# OLM-1_0.net
KiCad netlist of a schematic drawn in EAGLE
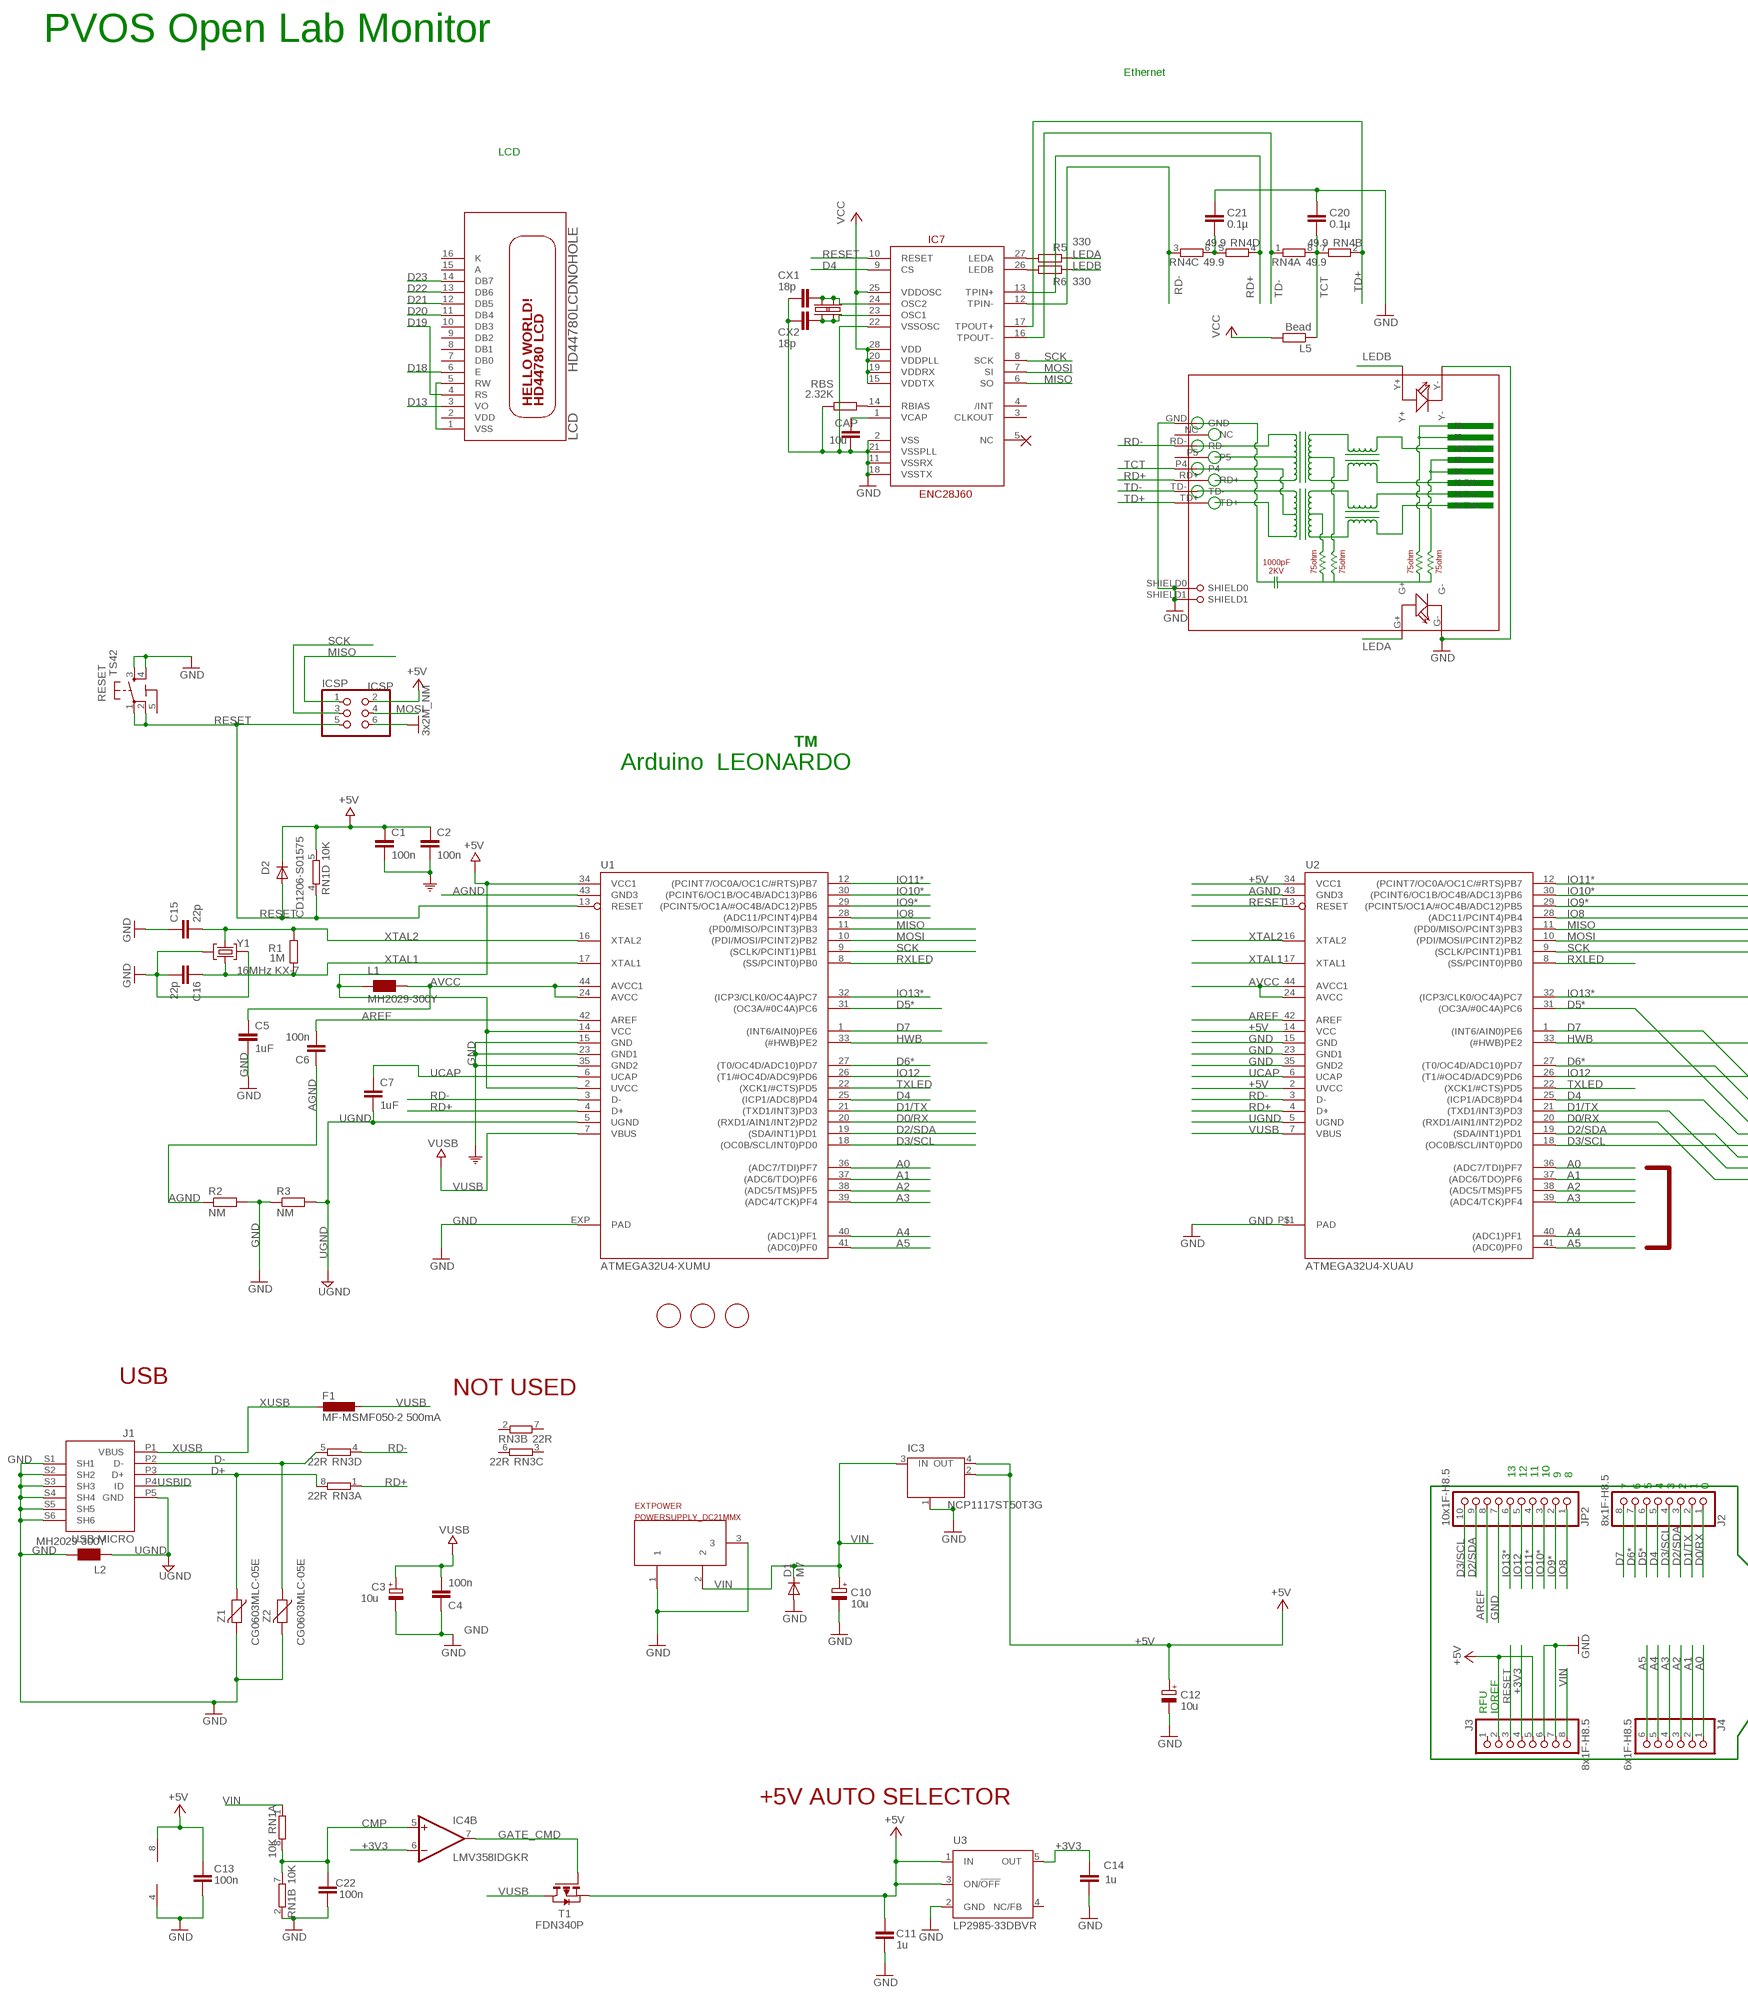
[diagram p0: schematic, sheet 1, part 1 of 2]
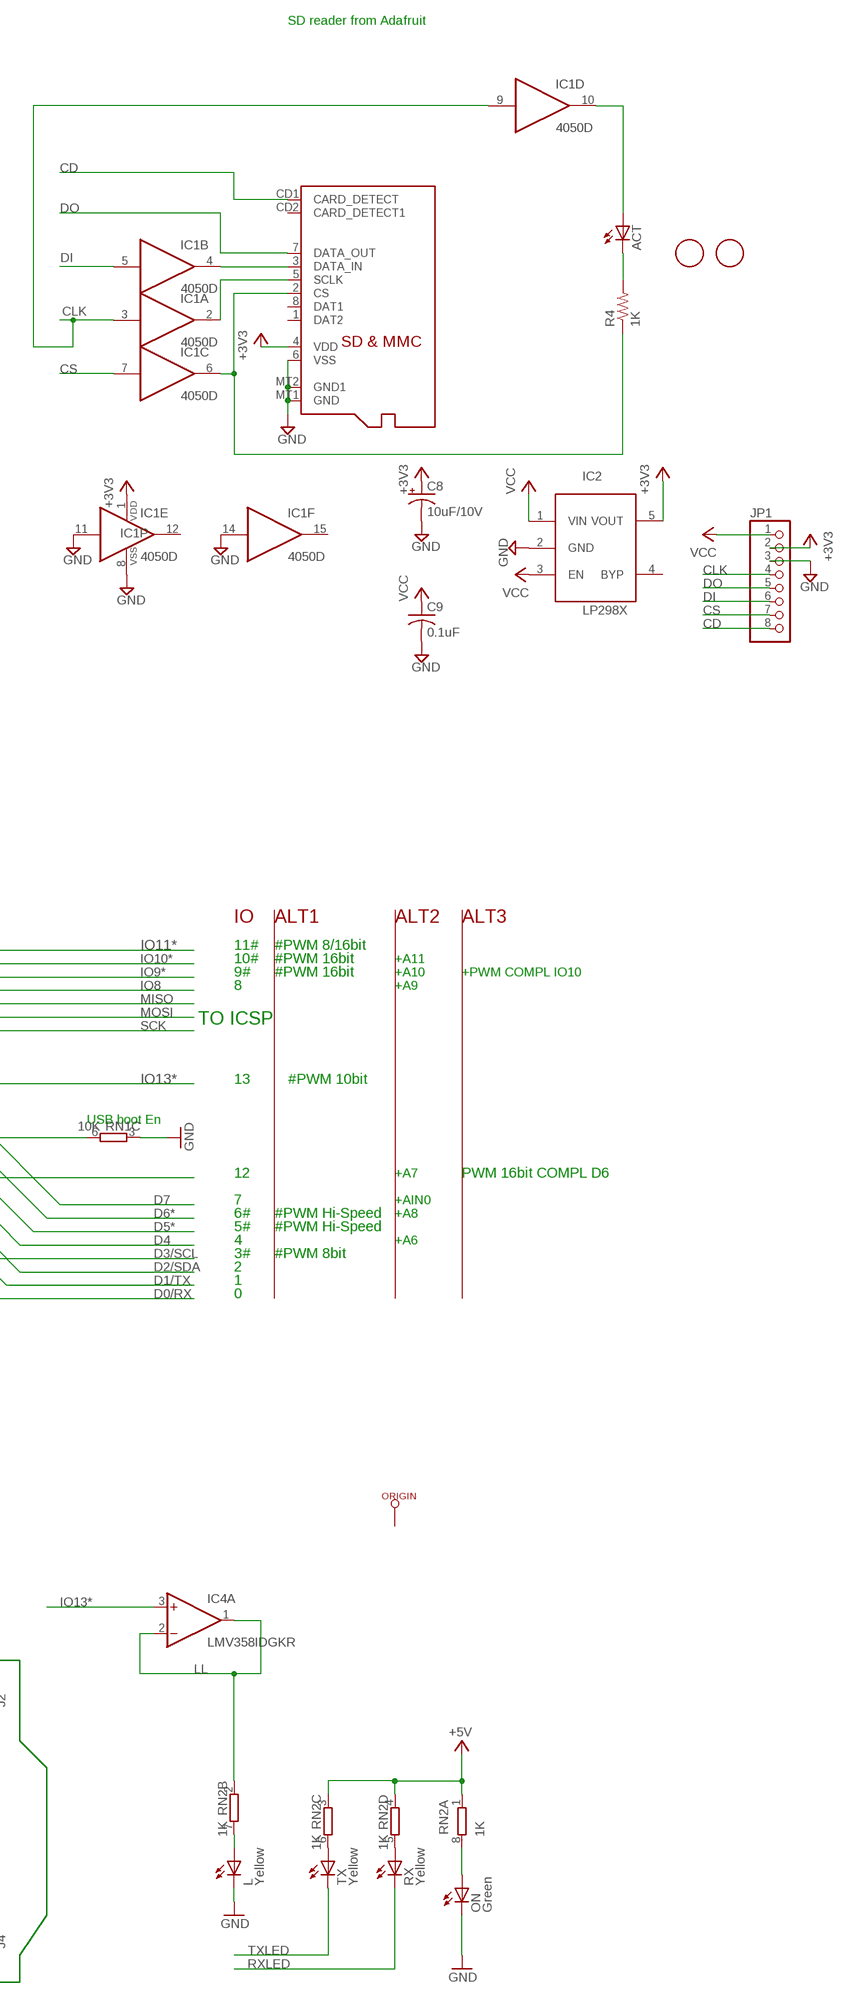
[diagram p1: schematic, sheet 1, part 2 of 2]

(export (version "E")
  (design (tool "Eeschema 10.0.6"))
  (components
    (comp (ref "ACT")
      (value "LEDCHIP-LED0805")
      (footprint "eagle-import:CHIP-LED0805")
      (libsource (lib "eagle-import") (part "LEDCHIP-LED0805"))
    )
    (comp (ref "C1")
      (value "100n")
      (footprint "eagle-import:C0603-ROUND")
      (libsource (lib "eagle-import") (part "C-EUC0603"))
    )
    (comp (ref "C2")
      (value "100n")
      (footprint "eagle-import:C0603-ROUND")
      (libsource (lib "eagle-import") (part "C-EUC0603"))
    )
    (comp (ref "C3")
      (value "10u")
      (footprint "eagle-import:SMC_B")
      (libsource (lib "eagle-import") (part "CPOL-EUSMCB"))
    )
    (comp (ref "C4")
      (value "100n")
      (footprint "eagle-import:C0603-ROUND")
      (libsource (lib "eagle-import") (part "C-EUC0603"))
    )
    (comp (ref "C5")
      (value "1uF")
      (footprint "eagle-import:C0603-ROUND")
      (libsource (lib "eagle-import") (part "C-EUC0603"))
    )
    (comp (ref "C6")
      (value "100n")
      (footprint "eagle-import:C0603-ROUND")
      (libsource (lib "eagle-import") (part "C-EUC0603"))
    )
    (comp (ref "C7")
      (value "1uF")
      (footprint "eagle-import:C0603-ROUND")
      (libsource (lib "eagle-import") (part "C-EUC0603"))
    )
    (comp (ref "C8")
      (value "10uF/10V")
      (footprint "eagle-import:A_3216-18R")
      (libsource (lib "eagle-import") (part "CPOL-USA/3216-18R"))
    )
    (comp (ref "C9")
      (value "0.1uF")
      (footprint "eagle-import:C0805K")
      (libsource (lib "eagle-import") (part "C-USC0805K"))
    )
    (comp (ref "C10")
      (value "10u")
      (footprint "eagle-import:SMC_B")
      (libsource (lib "eagle-import") (part "CPOL-EUSMCB"))
    )
    (comp (ref "C11")
      (value "1u")
      (footprint "eagle-import:C0603-ROUND")
      (libsource (lib "eagle-import") (part "C-EUC0603"))
    )
    (comp (ref "C12")
      (value "10u")
      (footprint "eagle-import:SMC_B")
      (libsource (lib "eagle-import") (part "CPOL-EUSMCB"))
    )
    (comp (ref "C13")
      (value "100n")
      (footprint "eagle-import:C0603-ROUND")
      (libsource (lib "eagle-import") (part "C-EUC0603"))
    )
    (comp (ref "C14")
      (value "1u")
      (footprint "eagle-import:C0603-ROUND")
      (libsource (lib "eagle-import") (part "C-EUC0603"))
    )
    (comp (ref "C15")
      (value "22p")
      (footprint "eagle-import:C0603-ROUND")
      (libsource (lib "eagle-import") (part "C-EUC0603"))
    )
    (comp (ref "C16")
      (value "22p")
      (footprint "eagle-import:C0603-ROUND")
      (libsource (lib "eagle-import") (part "C-EUC0603"))
    )
    (comp (ref "C20")
      (value "0.1µ")
      (footprint "eagle-import:C0805")
      (libsource (lib "eagle-import") (part "resistor_C-EUC0805"))
    )
    (comp (ref "C21")
      (value "0.1µ")
      (footprint "eagle-import:C0805")
      (libsource (lib "eagle-import") (part "resistor_C-EUC0805"))
    )
    (comp (ref "C22")
      (value "100n")
      (footprint "eagle-import:C0603-ROUND")
      (libsource (lib "eagle-import") (part "C-EUC0603"))
    )
    (comp (ref "CAP")
      (value "10u")
      (footprint "eagle-import:C0805")
      (libsource (lib "eagle-import") (part "resistor_C-EUC0805"))
    )
    (comp (ref "CX1")
      (value "18p")
      (footprint "eagle-import:C0805")
      (libsource (lib "eagle-import") (part "resistor_C-EUC0805"))
    )
    (comp (ref "CX2")
      (value "18p")
      (footprint "eagle-import:C0805")
      (libsource (lib "eagle-import") (part "resistor_C-EUC0805"))
    )
    (comp (ref "D1")
      (value "M7")
      (footprint "eagle-import:SMB")
      (libsource (lib "eagle-import") (part "DIODE-SMB"))
    )
    (comp (ref "D2")
      (value "CD1206-S01575")
      (footprint "eagle-import:MINIMELF")
      (libsource (lib "eagle-import") (part "DIODE-MINIMELF"))
    )
    (comp (ref "EXTPOWER")
      (value "POWERSUPPLY_DC21MMX")
      (footprint "eagle-import:POWERSUPPLY_DC-21MM")
      (libsource (lib "eagle-import") (part "POWERSUPPLY_DC21MMX"))
    )
    (comp (ref "F1")
      (value "MF-MSMF050-2 500mA")
      (footprint "eagle-import:L1812")
      (libsource (lib "eagle-import") (part "L-EUL1812"))
    )
    (comp (ref "FID1")
      (value "FIDUCIALMOUNT")
      (footprint "eagle-import:FIDUCIA-MOUNT")
      (libsource (lib "eagle-import") (part "FIDUCIALMOUNT"))
    )
    (comp (ref "FID2")
      (value "FIDUCIALMOUNT")
      (footprint "eagle-import:FIDUCIA-MOUNT")
      (libsource (lib "eagle-import") (part "FIDUCIALMOUNT"))
    )
    (comp (ref "FID3")
      (value "FIDUCIALMOUNT")
      (footprint "eagle-import:FIDUCIA-MOUNT")
      (libsource (lib "eagle-import") (part "FIDUCIALMOUNT"))
    )
    (comp (ref "IC1")
      (value "4050D")
      (footprint "eagle-import:SO16")
      (libsource (lib "eagle-import") (part "4050D"))
    )
    (comp (ref "IC2")
      (value "LP298XS")
      (footprint "eagle-import:SOT23-5L")
      (libsource (lib "eagle-import") (part "LP298XS"))
    )
    (comp (ref "IC3")
      (value "NCP1117ST50T3G")
      (footprint "eagle-import:SOT223")
      (libsource (lib "eagle-import") (part "MC33269ST-3.3T3"))
    )
    (comp (ref "IC4")
      (value "LMV358IDGKR")
      (footprint "eagle-import:MSOP08")
      (libsource (lib "eagle-import") (part "LMV358?MMX"))
    )
    (comp (ref "IC7")
      (value "ENC28J60")
      (footprint "eagle-import:SOIC28WLONG")
      (libsource (lib "eagle-import") (part "ENC28J60SO28LONG"))
    )
    (comp (ref "ICSP")
      (value "ICSP")
      (footprint "eagle-import:2X03")
      (libsource (lib "eagle-import") (part "PINHD-2X3"))
    )
    (comp (ref "J1")
      (value "USB MICRO")
      (footprint "eagle-import:CON2_USB_MICRO_B_AT")
      (libsource (lib "eagle-import") (part "MYCON2_USB-MINI-B"))
    )
    (comp (ref "J2")
      (value "8x1F-H8.5")
      (footprint "eagle-import:1X08")
      (libsource (lib "eagle-import") (part "PINHD-1X8"))
    )
    (comp (ref "J3")
      (value "8x1F-H8.5")
      (footprint "eagle-import:1X08")
      (libsource (lib "eagle-import") (part "PINHD-1X8"))
    )
    (comp (ref "J4")
      (value "6x1F-H8.5")
      (footprint "eagle-import:1X06")
      (libsource (lib "eagle-import") (part "PINHD-1X6"))
    )
    (comp (ref "JP1")
      (value "PINHD-1X8BIG")
      (footprint "eagle-import:1X08-BIG")
      (libsource (lib "eagle-import") (part "PINHD-1X8BIG"))
    )
    (comp (ref "JP2")
      (value "10x1F-H8.5")
      (footprint "eagle-import:1X10")
      (libsource (lib "eagle-import") (part "PINHD-1X10"))
    )
    (comp (ref "L")
      (value "Yellow")
      (footprint "eagle-import:CHIPLED_0805")
      (libsource (lib "eagle-import") (part "led_LEDCHIPLED_0805"))
    )
    (comp (ref "L1")
      (value "MH2029-300Y")
      (footprint "eagle-import:0805")
      (libsource (lib "eagle-import") (part "WE-CBF_0805"))
    )
    (comp (ref "L2")
      (value "MH2029-300Y")
      (footprint "eagle-import:0805")
      (libsource (lib "eagle-import") (part "WE-CBF_0805"))
    )
    (comp (ref "L5")
      (value "Bead")
      (footprint "eagle-import:R0805")
      (libsource (lib "eagle-import") (part "rcl_R-EU_R0805"))
    )
    (comp (ref "LCD")
      (value "HD44780LCDNOHOLE")
      (footprint "eagle-import:LCD1602A")
      (libsource (lib "eagle-import") (part "HD44780LCDNOHOLE"))
    )
    (comp (ref "ON")
      (value "Green")
      (footprint "eagle-import:CHIPLED_0805")
      (libsource (lib "eagle-import") (part "led_LEDCHIPLED_0805"))
    )
    (comp (ref "ORIGIN")
      (value "TP_SP")
      (footprint "eagle-import:TP-SP")
      (libsource (lib "eagle-import") (part "TP_SP"))
    )
    (comp (ref "R1")
      (value "1M")
      (footprint "eagle-import:R0603-ROUND")
      (libsource (lib "eagle-import") (part "R-EU_R0603"))
    )
    (comp (ref "R2")
      (value "NM")
      (footprint "eagle-import:R0402")
      (libsource (lib "eagle-import") (part "R-EU_R0402"))
    )
    (comp (ref "R3")
      (value "NM")
      (footprint "eagle-import:R0402")
      (libsource (lib "eagle-import") (part "R-EU_R0402"))
    )
    (comp (ref "R4")
      (value "1K")
      (footprint "eagle-import:R0805")
      (libsource (lib "eagle-import") (part "R-US_R0805"))
    )
    (comp (ref "R5")
      (value "330")
      (footprint "eagle-import:R0805")
      (libsource (lib "eagle-import") (part "rcl_R-EU_R0805"))
    )
    (comp (ref "R6")
      (value "330")
      (footprint "eagle-import:R0805")
      (libsource (lib "eagle-import") (part "rcl_R-EU_R0805"))
    )
    (comp (ref "RBS")
      (value "2.32K")
      (footprint "eagle-import:R0805")
      (libsource (lib "eagle-import") (part "rcl_R-EU_R0805"))
    )
    (comp (ref "RESET")
      (value "TS42")
      (footprint "eagle-import:TS42")
      (libsource (lib "eagle-import") (part "TS42"))
    )
    (comp (ref "RJ1")
      (value "HR911105A")
      (footprint "eagle-import:HR911105A")
      (libsource (lib "eagle-import") (part "HR911105A"))
    )
    (comp (ref "RN1")
      (value "10K")
      (footprint "eagle-import:CAY16")
      (libsource (lib "eagle-import") (part "4R-NCAY16"))
    )
    (comp (ref "RN2")
      (value "1K")
      (footprint "eagle-import:CAY16")
      (libsource (lib "eagle-import") (part "4R-NCAY16"))
    )
    (comp (ref "RN3")
      (value "22R")
      (footprint "eagle-import:CAY16")
      (libsource (lib "eagle-import") (part "4R-NCAY16"))
    )
    (comp (ref "RN4")
      (value "49.9")
      (footprint "eagle-import:EXB38V")
      (libsource (lib "eagle-import") (part "4R-NEXB38V"))
    )
    (comp (ref "RX")
      (value "Yellow")
      (footprint "eagle-import:CHIPLED_0805")
      (libsource (lib "eagle-import") (part "led_LEDCHIPLED_0805"))
    )
    (comp (ref "T1")
      (value "FDN340P")
      (footprint "eagle-import:SOT-23")
      (libsource (lib "eagle-import") (part "PMOSSOT23"))
    )
    (comp (ref "TX")
      (value "Yellow")
      (footprint "eagle-import:CHIPLED_0805")
      (libsource (lib "eagle-import") (part "led_LEDCHIPLED_0805"))
    )
    (comp (ref "U$1")
      (value "FIDUCIAL")
      (footprint "eagle-import:FIDUCIAL_1MM")
      (libsource (lib "eagle-import") (part "FIDUCIAL"))
    )
    (comp (ref "U$2")
      (value "FIDUCIAL")
      (footprint "eagle-import:FIDUCIAL_1MM")
      (libsource (lib "eagle-import") (part "FIDUCIAL"))
    )
    (comp (ref "U1")
      (value "ATMEGA32U4-XUMU")
      (footprint "eagle-import:QFN44ML7X7")
      (libsource (lib "eagle-import") (part "ATMEGA32U4-XUMU"))
    )
    (comp (ref "U2")
      (value "ATMEGA32U4-XUAU")
      (footprint "eagle-import:TQFP44-PAD")
      (libsource (lib "eagle-import") (part "ATMEGA32U4-XUAU"))
    )
    (comp (ref "U3")
      (value "LP2985-33DBVR")
      (footprint "eagle-import:SOT23-DBV")
      (libsource (lib "eagle-import") (part "LP2985-XXDBVR33"))
    )
    (comp (ref "X1")
      (value "MICROSD")
      (footprint "eagle-import:MICROSD")
      (libsource (lib "eagle-import") (part "MICROSD"))
    )
    (comp (ref "X2A")
      (value "25MHz")
      (footprint "eagle-import:CRYSTAL-SMD-10.5X4.8-2PIN")
      (libsource (lib "eagle-import") (part "CRYSTAL10.5X4.8"))
    )
    (comp (ref "X2A1")
      (value "25MHz")
      (footprint "eagle-import:HC49US")
      (libsource (lib "eagle-import") (part "CRYSTALHC49US"))
    )
    (comp (ref "Y1")
      (value "16MHz KX-7")
      (footprint "eagle-import:CRYSTAL-3.2-2.5")
      (libsource (lib "eagle-import") (part "CRYSTAL-3.2-2.5"))
    )
    (comp (ref "Z1")
      (value "CG0603MLC-05E")
      (footprint "eagle-import:CT_CN0603")
      (libsource (lib "eagle-import") (part "VARISTORCN0603"))
    )
    (comp (ref "Z2")
      (value "CG0603MLC-05E")
      (footprint "eagle-import:CT_CN0603")
      (libsource (lib "eagle-import") (part "VARISTORCN0603"))
    )
  )
  (nets
    (net (code "1") (name "+3V3") (class "Default")
      (node (ref "C14") (pin "2") (pinfunction "2_2") (pintype "passive"))
      (node (ref "C8") (pin "+") (pinfunction "+_+") (pintype "passive"))
      (node (ref "IC1") (pin "1") (pinfunction "VDD_1") (pintype "power_in"))
      (node (ref "IC2") (pin "5") (pinfunction "VOUT_5") (pintype "bidirectional"))
      (node (ref "IC4") (pin "6") (pinfunction "-IN_6") (pintype "input"))
      (node (ref "J3") (pin "4") (pinfunction "4_4") (pintype "passive"))
      (node (ref "JP1") (pin "2") (pinfunction "2_2") (pintype "passive"))
      (node (ref "U3") (pin "5") (pinfunction "OUT_5") (pintype "passive"))
      (node (ref "X1") (pin "4") (pinfunction "VDD_4") (pintype "power_in"))
    )
    (net (code "2") (name "+5V") (class "Default")
      (node (ref "C1") (pin "1") (pinfunction "1_1") (pintype "passive"))
      (node (ref "C11") (pin "2") (pinfunction "2_2") (pintype "passive"))
      (node (ref "C12") (pin "+") (pinfunction "+_+") (pintype "passive"))
      (node (ref "C13") (pin "1") (pinfunction "1_1") (pintype "passive"))
      (node (ref "C2") (pin "1") (pinfunction "1_1") (pintype "passive"))
      (node (ref "D2") (pin "C") (pinfunction "C_C") (pintype "passive"))
      (node (ref "IC3") (pin "2") (pinfunction "OUT_2") (pintype "passive"))
      (node (ref "IC3") (pin "4") (pinfunction "OUT_4") (pintype "passive"))
      (node (ref "IC4") (pin "8") (pinfunction "V+_8") (pintype "power_in"))
      (node (ref "ICSP") (pin "2") (pinfunction "2_2") (pintype "passive"))
      (node (ref "J3") (pin "2") (pinfunction "2_2") (pintype "passive"))
      (node (ref "J3") (pin "5") (pinfunction "5_5") (pintype "passive"))
      (node (ref "L1") (pin "1") (pinfunction "1_1") (pintype "passive"))
      (node (ref "RN1") (pin "5") (pinfunction "2_5") (pintype "passive"))
      (node (ref "RN2") (pin "1") (pinfunction "1_1") (pintype "passive"))
      (node (ref "RN2") (pin "3") (pinfunction "1_3") (pintype "passive"))
      (node (ref "RN2") (pin "4") (pinfunction "1_4") (pintype "passive"))
      (node (ref "T1") (pin "2") (pinfunction "S_2") (pintype "passive"))
      (node (ref "U1") (pin "14") (pinfunction "VCC_14") (pintype "power_in"))
      (node (ref "U1") (pin "2") (pinfunction "UVCC_2") (pintype "power_in"))
      (node (ref "U1") (pin "34") (pinfunction "VCC1_34") (pintype "power_in"))
      (node (ref "U2") (pin "14") (pinfunction "VCC_14") (pintype "power_in"))
      (node (ref "U2") (pin "2") (pinfunction "UVCC_2") (pintype "power_in"))
      (node (ref "U2") (pin "34") (pinfunction "VCC1_34") (pintype "power_in"))
      (node (ref "U3") (pin "1") (pinfunction "IN_1") (pintype "input"))
      (node (ref "U3") (pin "3") (pinfunction "ON/~{OFF}_3") (pintype "input"))
    )
    (net (code "3") (name "/5-GND") (class "Default")
      (node (ref "RESET") (pin "5") (pinfunction "5-GND_5") (pintype "power_in"))
    )
    (net (code "4") (name "/A0") (class "Default")
      (node (ref "J4") (pin "1") (pinfunction "1_1") (pintype "passive"))
      (node (ref "U1") (pin "36") (pinfunction "(ADC7/TDI)PF7_36") (pintype "bidirectional"))
      (node (ref "U2") (pin "36") (pinfunction "(ADC7/TDI)PF7_36") (pintype "bidirectional"))
    )
    (net (code "5") (name "/A1") (class "Default")
      (node (ref "J4") (pin "2") (pinfunction "2_2") (pintype "passive"))
      (node (ref "U1") (pin "37") (pinfunction "(ADC6/TDO)PF6_37") (pintype "bidirectional"))
      (node (ref "U2") (pin "37") (pinfunction "(ADC6/TDO)PF6_37") (pintype "bidirectional"))
    )
    (net (code "6") (name "/A2") (class "Default")
      (node (ref "J4") (pin "3") (pinfunction "3_3") (pintype "passive"))
      (node (ref "U1") (pin "38") (pinfunction "(ADC5/TMS)PF5_38") (pintype "bidirectional"))
      (node (ref "U2") (pin "38") (pinfunction "(ADC5/TMS)PF5_38") (pintype "bidirectional"))
    )
    (net (code "7") (name "/A3") (class "Default")
      (node (ref "J4") (pin "4") (pinfunction "4_4") (pintype "passive"))
      (node (ref "U1") (pin "39") (pinfunction "(ADC4/TCK)PF4_39") (pintype "bidirectional"))
      (node (ref "U2") (pin "39") (pinfunction "(ADC4/TCK)PF4_39") (pintype "bidirectional"))
    )
    (net (code "8") (name "/A4") (class "Default")
      (node (ref "J4") (pin "5") (pinfunction "5_5") (pintype "passive"))
      (node (ref "U1") (pin "40") (pinfunction "(ADC1)PF1_40") (pintype "bidirectional"))
      (node (ref "U2") (pin "40") (pinfunction "(ADC1)PF1_40") (pintype "bidirectional"))
    )
    (net (code "9") (name "/A5") (class "Default")
      (node (ref "J4") (pin "6") (pinfunction "6_6") (pintype "passive"))
      (node (ref "U1") (pin "41") (pinfunction "(ADC0)PF0_41") (pintype "bidirectional"))
      (node (ref "U2") (pin "41") (pinfunction "(ADC0)PF0_41") (pintype "bidirectional"))
    )
    (net (code "10") (name "/AGND") (class "Default")
      (node (ref "C6") (pin "1") (pinfunction "1_1") (pintype "passive"))
      (node (ref "R2") (pin "1") (pinfunction "1_1") (pintype "passive"))
      (node (ref "U1") (pin "43") (pinfunction "GND3_43") (pintype "power_in"))
      (node (ref "U2") (pin "43") (pinfunction "GND3_43") (pintype "power_in"))
    )
    (net (code "11") (name "/AREF") (class "Default")
      (node (ref "C6") (pin "2") (pinfunction "2_2") (pintype "passive"))
      (node (ref "JP2") (pin "8") (pinfunction "8_8") (pintype "passive"))
      (node (ref "U1") (pin "42") (pinfunction "AREF_42") (pintype "power_in"))
      (node (ref "U2") (pin "42") (pinfunction "AREF_42") (pintype "power_in"))
    )
    (net (code "12") (name "/AVCC") (class "Default")
      (node (ref "C5") (pin "1") (pinfunction "1_1") (pintype "passive"))
      (node (ref "L1") (pin "2") (pinfunction "2_2") (pintype "passive"))
      (node (ref "U1") (pin "24") (pinfunction "AVCC_24") (pintype "power_in"))
      (node (ref "U1") (pin "44") (pinfunction "AVCC1_44") (pintype "power_in"))
      (node (ref "U2") (pin "24") (pinfunction "AVCC_24") (pintype "power_in"))
      (node (ref "U2") (pin "44") (pinfunction "AVCC1_44") (pintype "power_in"))
    )
    (net (code "13") (name "/CD") (class "Default")
      (node (ref "JP1") (pin "8") (pinfunction "8_8") (pintype "passive"))
      (node (ref "X1") (pin "CD1") (pinfunction "CARD_DETECT_CD1") (pintype "passive"))
    )
    (net (code "14") (name "/CLK") (class "Default")
      (node (ref "IC1") (pin "3") (pinfunction "I_3") (pintype "input"))
      (node (ref "IC1") (pin "9") (pinfunction "I_9") (pintype "input"))
      (node (ref "JP1") (pin "4") (pinfunction "4_4") (pintype "passive"))
    )
    (net (code "15") (name "/CMP") (class "Default")
      (node (ref "C22") (pin "2") (pinfunction "2_2") (pintype "passive"))
      (node (ref "IC4") (pin "5") (pinfunction "+IN_5") (pintype "input"))
      (node (ref "RN1") (pin "7") (pinfunction "2_7") (pintype "passive"))
      (node (ref "RN1") (pin "8") (pinfunction "2_8") (pintype "passive"))
    )
    (net (code "16") (name "/CS") (class "Default")
      (node (ref "IC1") (pin "7") (pinfunction "I_7") (pintype "input"))
      (node (ref "JP1") (pin "7") (pinfunction "7_7") (pintype "passive"))
    )
    (net (code "17") (name "/D+") (class "Default")
      (node (ref "J1") (pin "P3") (pinfunction "D+_P3") (pintype "bidirectional"))
      (node (ref "RN3") (pin "8") (pinfunction "2_8") (pintype "passive"))
      (node (ref "Z1") (pin "1") (pinfunction "1_1") (pintype "passive"))
    )
    (net (code "18") (name "/D-") (class "Default")
      (node (ref "J1") (pin "P2") (pinfunction "D-_P2") (pintype "bidirectional"))
      (node (ref "RN3") (pin "5") (pinfunction "2_5") (pintype "passive"))
      (node (ref "Z2") (pin "1") (pinfunction "1_1") (pintype "passive"))
    )
    (net (code "19") (name "/D0{slash}RX") (class "Default")
      (node (ref "J2") (pin "1") (pinfunction "1_1") (pintype "passive"))
      (node (ref "U1") (pin "20") (pinfunction "(RXD1/AIN1/INT2)PD2_20") (pintype "bidirectional"))
      (node (ref "U2") (pin "20") (pinfunction "(RXD1/AIN1/INT2)PD2_20") (pintype "bidirectional"))
    )
    (net (code "20") (name "/D1{slash}TX") (class "Default")
      (node (ref "J2") (pin "2") (pinfunction "2_2") (pintype "passive"))
      (node (ref "U1") (pin "21") (pinfunction "(TXD1/INT3)PD3_21") (pintype "bidirectional"))
      (node (ref "U2") (pin "21") (pinfunction "(TXD1/INT3)PD3_21") (pintype "bidirectional"))
    )
    (net (code "21") (name "/D2{slash}SDA") (class "Default")
      (node (ref "J2") (pin "3") (pinfunction "3_3") (pintype "passive"))
      (node (ref "JP2") (pin "9") (pinfunction "9_9") (pintype "passive"))
      (node (ref "U1") (pin "19") (pinfunction "(SDA/INT1)PD1_19") (pintype "bidirectional"))
      (node (ref "U2") (pin "19") (pinfunction "(SDA/INT1)PD1_19") (pintype "bidirectional"))
    )
    (net (code "22") (name "/D3{slash}SCL") (class "Default")
      (node (ref "J2") (pin "4") (pinfunction "4_4") (pintype "passive"))
      (node (ref "JP2") (pin "10") (pinfunction "10_10") (pintype "passive"))
      (node (ref "U1") (pin "18") (pinfunction "(OC0B/SCL/INT0)PD0_18") (pintype "bidirectional"))
      (node (ref "U2") (pin "18") (pinfunction "(OC0B/SCL/INT0)PD0_18") (pintype "bidirectional"))
    )
    (net (code "23") (name "/D4") (class "Default")
      (node (ref "IC7") (pin "9") (pinfunction "CS_9") (pintype "bidirectional"))
      (node (ref "J2") (pin "5") (pinfunction "5_5") (pintype "passive"))
      (node (ref "U1") (pin "25") (pinfunction "(ICP1/ADC8)PD4_25") (pintype "bidirectional"))
      (node (ref "U2") (pin "25") (pinfunction "(ICP1/ADC8)PD4_25") (pintype "bidirectional"))
    )
    (net (code "24") (name "/D5*") (class "Default")
      (node (ref "J2") (pin "6") (pinfunction "6_6") (pintype "passive"))
      (node (ref "U1") (pin "31") (pinfunction "(OC3A/#0C4A)PC6_31") (pintype "bidirectional"))
      (node (ref "U2") (pin "31") (pinfunction "(OC3A/#0C4A)PC6_31") (pintype "bidirectional"))
    )
    (net (code "25") (name "/D6*") (class "Default")
      (node (ref "J2") (pin "7") (pinfunction "7_7") (pintype "passive"))
      (node (ref "U1") (pin "27") (pinfunction "(T0/OC4D/ADC10)PD7_27") (pintype "bidirectional"))
      (node (ref "U2") (pin "27") (pinfunction "(T0/OC4D/ADC10)PD7_27") (pintype "bidirectional"))
    )
    (net (code "26") (name "/D7") (class "Default")
      (node (ref "J2") (pin "8") (pinfunction "8_8") (pintype "passive"))
      (node (ref "U1") (pin "1") (pinfunction "(INT6/AIN0)PE6_1") (pintype "bidirectional"))
      (node (ref "U2") (pin "1") (pinfunction "(INT6/AIN0)PE6_1") (pintype "bidirectional"))
    )
    (net (code "27") (name "/D13") (class "Default")
      (node (ref "LCD") (pin "3") (pinfunction "VO_3") (pintype "input"))
    )
    (net (code "28") (name "/D18") (class "Default")
      (node (ref "LCD") (pin "6") (pinfunction "E_6") (pintype "input"))
    )
    (net (code "29") (name "/D19") (class "Default")
      (node (ref "LCD") (pin "4") (pinfunction "RS_4") (pintype "input"))
    )
    (net (code "30") (name "/D20") (class "Default")
      (node (ref "LCD") (pin "11") (pinfunction "DB4_11") (pintype "bidirectional"))
    )
    (net (code "31") (name "/D21") (class "Default")
      (node (ref "LCD") (pin "12") (pinfunction "DB5_12") (pintype "bidirectional"))
    )
    (net (code "32") (name "/D22") (class "Default")
      (node (ref "LCD") (pin "13") (pinfunction "DB6_13") (pintype "bidirectional"))
    )
    (net (code "33") (name "/D23") (class "Default")
      (node (ref "LCD") (pin "14") (pinfunction "DB7_14") (pintype "bidirectional"))
    )
    (net (code "34") (name "/DI") (class "Default")
      (node (ref "IC1") (pin "5") (pinfunction "I_5") (pintype "input"))
      (node (ref "JP1") (pin "6") (pinfunction "6_6") (pintype "passive"))
    )
    (net (code "35") (name "/DO") (class "Default")
      (node (ref "JP1") (pin "5") (pinfunction "5_5") (pintype "passive"))
      (node (ref "X1") (pin "7") (pinfunction "DATA_OUT_7") (pintype "output"))
    )
    (net (code "36") (name "/GATE_CMD") (class "Default")
      (node (ref "IC4") (pin "7") (pinfunction "OUT_7") (pintype "output"))
      (node (ref "T1") (pin "3") (pinfunction "G_3") (pintype "passive"))
    )
    (net (code "37") (name "/HWB") (class "Default")
      (node (ref "RN1") (pin "6") (pinfunction "2_6") (pintype "passive"))
      (node (ref "U1") (pin "33") (pinfunction "(#HWB)PE2_33") (pintype "bidirectional"))
      (node (ref "U2") (pin "33") (pinfunction "(#HWB)PE2_33") (pintype "bidirectional"))
    )
    (net (code "38") (name "/IO8") (class "Default")
      (node (ref "JP2") (pin "1") (pinfunction "1_1") (pintype "passive"))
      (node (ref "U1") (pin "28") (pinfunction "(ADC11/PCINT4)PB4_28") (pintype "bidirectional"))
      (node (ref "U2") (pin "28") (pinfunction "(ADC11/PCINT4)PB4_28") (pintype "bidirectional"))
    )
    (net (code "39") (name "/IO9*") (class "Default")
      (node (ref "JP2") (pin "2") (pinfunction "2_2") (pintype "passive"))
      (node (ref "U1") (pin "29") (pinfunction "(PCINT5/OC1A/#OC4B/ADC12)PB5_29") (pintype "bidirectional"))
      (node (ref "U2") (pin "29") (pinfunction "(PCINT5/OC1A/#OC4B/ADC12)PB5_29") (pintype "bidirectional"))
    )
    (net (code "40") (name "/IO10*") (class "Default")
      (node (ref "JP2") (pin "3") (pinfunction "3_3") (pintype "passive"))
      (node (ref "U1") (pin "30") (pinfunction "(PCINT6/OC1B/OC4B/ADC13)PB6_30") (pintype "bidirectional"))
      (node (ref "U2") (pin "30") (pinfunction "(PCINT6/OC1B/OC4B/ADC13)PB6_30") (pintype "bidirectional"))
    )
    (net (code "41") (name "/IO11*") (class "Default")
      (node (ref "JP2") (pin "4") (pinfunction "4_4") (pintype "passive"))
      (node (ref "U1") (pin "12") (pinfunction "(PCINT7/OC0A/OC1C/#RTS)PB7_12") (pintype "bidirectional"))
      (node (ref "U2") (pin "12") (pinfunction "(PCINT7/OC0A/OC1C/#RTS)PB7_12") (pintype "bidirectional"))
    )
    (net (code "42") (name "/IO12") (class "Default")
      (node (ref "JP2") (pin "5") (pinfunction "5_5") (pintype "passive"))
      (node (ref "U1") (pin "26") (pinfunction "(T1/#OC4D/ADC9)PD6_26") (pintype "bidirectional"))
      (node (ref "U2") (pin "26") (pinfunction "(T1/#OC4D/ADC9)PD6_26") (pintype "bidirectional"))
    )
    (net (code "43") (name "/IO13*") (class "Default")
      (node (ref "IC4") (pin "3") (pinfunction "+IN_3") (pintype "input"))
      (node (ref "JP2") (pin "6") (pinfunction "6_6") (pintype "passive"))
      (node (ref "U1") (pin "32") (pinfunction "(ICP3/CLK0/OC4A)PC7_32") (pintype "bidirectional"))
      (node (ref "U2") (pin "32") (pinfunction "(ICP3/CLK0/OC4A)PC7_32") (pintype "bidirectional"))
    )
    (net (code "44") (name "/LEDA") (class "Default")
      (node (ref "R5") (pin "2") (pinfunction "2_2") (pintype "passive"))
      (node (ref "RJ1") (pin "G+") (pinfunction "G+_G+") (pintype "bidirectional"))
    )
    (net (code "45") (name "/LEDB") (class "Default")
      (node (ref "R6") (pin "2") (pinfunction "2_2") (pintype "passive"))
      (node (ref "RJ1") (pin "Y+") (pinfunction "Y+_Y+") (pintype "bidirectional"))
    )
    (net (code "46") (name "/LL") (class "Default")
      (node (ref "IC4") (pin "1") (pinfunction "OUT_1") (pintype "output"))
      (node (ref "IC4") (pin "2") (pinfunction "-IN_2") (pintype "input"))
      (node (ref "RN2") (pin "2") (pinfunction "1_2") (pintype "passive"))
    )
    (net (code "47") (name "/MISO") (class "Default")
      (node (ref "IC7") (pin "6") (pinfunction "SO_6") (pintype "bidirectional"))
      (node (ref "ICSP") (pin "1") (pinfunction "1_1") (pintype "passive"))
      (node (ref "U1") (pin "11") (pinfunction "(PD0/MISO/PCINT3)PB3_11") (pintype "bidirectional"))
      (node (ref "U2") (pin "11") (pinfunction "(PD0/MISO/PCINT3)PB3_11") (pintype "bidirectional"))
    )
    (net (code "48") (name "/MOSI") (class "Default")
      (node (ref "IC7") (pin "7") (pinfunction "SI_7") (pintype "bidirectional"))
      (node (ref "ICSP") (pin "4") (pinfunction "4_4") (pintype "passive"))
      (node (ref "U1") (pin "10") (pinfunction "(PDI/MOSI/PCINT2)PB2_10") (pintype "bidirectional"))
      (node (ref "U2") (pin "10") (pinfunction "(PDI/MOSI/PCINT2)PB2_10") (pintype "bidirectional"))
    )
    (net (code "49") (name "/RD+") (class "Default")
      (node (ref "IC7") (pin "13") (pinfunction "TPIN+_13") (pintype "bidirectional"))
      (node (ref "RJ1") (pin "RD+") (pinfunction "RD+_RD+") (pintype "bidirectional"))
      (node (ref "RN3") (pin "1") (pinfunction "1_1") (pintype "passive"))
      (node (ref "RN4") (pin "4") (pinfunction "1_4") (pintype "passive"))
      (node (ref "U1") (pin "4") (pinfunction "D+_4") (pintype "bidirectional"))
      (node (ref "U2") (pin "4") (pinfunction "D+_4") (pintype "bidirectional"))
    )
    (net (code "50") (name "/RD-") (class "Default")
      (node (ref "IC7") (pin "12") (pinfunction "TPIN-_12") (pintype "bidirectional"))
      (node (ref "RJ1") (pin "RD-") (pinfunction "RD-_RD-") (pintype "bidirectional"))
      (node (ref "RN3") (pin "4") (pinfunction "1_4") (pintype "passive"))
      (node (ref "RN4") (pin "3") (pinfunction "1_3") (pintype "passive"))
      (node (ref "U1") (pin "3") (pinfunction "D-_3") (pintype "bidirectional"))
      (node (ref "U2") (pin "3") (pinfunction "D-_3") (pintype "bidirectional"))
    )
    (net (code "51") (name "/RESET") (class "Default")
      (node (ref "D2") (pin "A") (pinfunction "A_A") (pintype "passive"))
      (node (ref "IC7") (pin "10") (pinfunction "RESET_10") (pintype "bidirectional"))
      (node (ref "ICSP") (pin "5") (pinfunction "5_5") (pintype "passive"))
      (node (ref "J3") (pin "3") (pinfunction "3_3") (pintype "passive"))
      (node (ref "RESET") (pin "1") (pinfunction "1_1") (pintype "passive"))
      (node (ref "RESET") (pin "2") (pinfunction "2_2") (pintype "passive"))
      (node (ref "RN1") (pin "4") (pinfunction "1_4") (pintype "passive"))
      (node (ref "U1") (pin "13") (pinfunction "RESET_13") (pintype "input"))
      (node (ref "U2") (pin "13") (pinfunction "RESET_13") (pintype "input"))
    )
    (net (code "52") (name "/RXLED") (class "Default")
      (node (ref "RX") (pin "C") (pinfunction "C_C") (pintype "passive"))
      (node (ref "U1") (pin "8") (pinfunction "(SS/PCINT0)PB0_8") (pintype "bidirectional"))
      (node (ref "U2") (pin "8") (pinfunction "(SS/PCINT0)PB0_8") (pintype "bidirectional"))
    )
    (net (code "53") (name "/SCK") (class "Default")
      (node (ref "IC7") (pin "8") (pinfunction "SCK_8") (pintype "bidirectional"))
      (node (ref "ICSP") (pin "3") (pinfunction "3_3") (pintype "passive"))
      (node (ref "U1") (pin "9") (pinfunction "(SCLK/PCINT1)PB1_9") (pintype "bidirectional"))
      (node (ref "U2") (pin "9") (pinfunction "(SCLK/PCINT1)PB1_9") (pintype "bidirectional"))
    )
    (net (code "54") (name "/TCT") (class "Default")
      (node (ref "C20") (pin "2") (pinfunction "2_2") (pintype "passive"))
      (node (ref "L5") (pin "1") (pinfunction "1_1") (pintype "passive"))
      (node (ref "RJ1") (pin "P4") (pinfunction "P4_P4") (pintype "bidirectional"))
      (node (ref "RN4") (pin "7") (pinfunction "2_7") (pintype "passive"))
      (node (ref "RN4") (pin "8") (pinfunction "2_8") (pintype "passive"))
    )
    (net (code "55") (name "/TD+") (class "Default")
      (node (ref "IC7") (pin "17") (pinfunction "TPOUT+_17") (pintype "bidirectional"))
      (node (ref "RJ1") (pin "TD+") (pinfunction "TD+_TD+") (pintype "bidirectional"))
      (node (ref "RN4") (pin "2") (pinfunction "1_2") (pintype "passive"))
    )
    (net (code "56") (name "/TD-") (class "Default")
      (node (ref "IC7") (pin "16") (pinfunction "TPOUT-_16") (pintype "bidirectional"))
      (node (ref "RJ1") (pin "TD-") (pinfunction "TD-_TD-") (pintype "bidirectional"))
      (node (ref "RN4") (pin "1") (pinfunction "1_1") (pintype "passive"))
    )
    (net (code "57") (name "/TXLED") (class "Default")
      (node (ref "TX") (pin "C") (pinfunction "C_C") (pintype "passive"))
      (node (ref "U1") (pin "22") (pinfunction "(XCK1/#CTS)PD5_22") (pintype "bidirectional"))
      (node (ref "U2") (pin "22") (pinfunction "(XCK1/#CTS)PD5_22") (pintype "bidirectional"))
    )
    (net (code "58") (name "/UCAP") (class "Default")
      (node (ref "C7") (pin "1") (pinfunction "1_1") (pintype "passive"))
      (node (ref "U1") (pin "6") (pinfunction "UCAP_6") (pintype "passive"))
      (node (ref "U2") (pin "6") (pinfunction "UCAP_6") (pintype "passive"))
    )
    (net (code "59") (name "/USBID") (class "Default")
      (node (ref "J1") (pin "P4") (pinfunction "ID_P4") (pintype "bidirectional"))
    )
    (net (code "60") (name "/VDD") (class "Default")
      (node (ref "LCD") (pin "2") (pinfunction "VDD_2") (pintype "power_in"))
    )
    (net (code "61") (name "/VIN") (class "Default")
      (node (ref "C10") (pin "+") (pinfunction "+_+") (pintype "passive"))
      (node (ref "D1") (pin "C") (pinfunction "C_C") (pintype "passive"))
      (node (ref "EXTPOWER") (pin "2") (pinfunction "2_2") (pintype "power_in"))
      (node (ref "IC3") (pin "3") (pinfunction "IN_3") (pintype "input"))
      (node (ref "J3") (pin "8") (pinfunction "8_8") (pintype "passive"))
      (node (ref "RN1") (pin "1") (pinfunction "1_1") (pintype "passive"))
    )
    (net (code "62") (name "/XTAL1") (class "Default")
      (node (ref "C16") (pin "1") (pinfunction "1_1") (pintype "passive"))
      (node (ref "R1") (pin "1") (pinfunction "1_1") (pintype "passive"))
      (node (ref "U1") (pin "17") (pinfunction "XTAL1_17") (pintype "bidirectional"))
      (node (ref "U2") (pin "17") (pinfunction "XTAL1_17") (pintype "bidirectional"))
      (node (ref "Y1") (pin "1") (pinfunction "C1_1") (pintype "passive"))
    )
    (net (code "63") (name "/XTAL2") (class "Default")
      (node (ref "C15") (pin "2") (pinfunction "2_2") (pintype "passive"))
      (node (ref "R1") (pin "2") (pinfunction "2_2") (pintype "passive"))
      (node (ref "U1") (pin "16") (pinfunction "XTAL2_16") (pintype "bidirectional"))
      (node (ref "U2") (pin "16") (pinfunction "XTAL2_16") (pintype "bidirectional"))
      (node (ref "Y1") (pin "3") (pinfunction "C2_3") (pintype "passive"))
    )
    (net (code "64") (name "/XUSB") (class "Default")
      (node (ref "F1") (pin "2") (pinfunction "2_2") (pintype "passive"))
      (node (ref "J1") (pin "P1") (pinfunction "VBUS_P1") (pintype "power_in"))
    )
    (net (code "65") (name "3x2M_NM") (class "Default")
      (node (ref "C1") (pin "2") (pinfunction "2_2") (pintype "passive"))
      (node (ref "C10") (pin "-") (pinfunction "-_-") (pintype "passive"))
      (node (ref "C11") (pin "1") (pinfunction "1_1") (pintype "passive"))
      (node (ref "C12") (pin "-") (pinfunction "-_-") (pintype "passive"))
      (node (ref "C13") (pin "2") (pinfunction "2_2") (pintype "passive"))
      (node (ref "C14") (pin "1") (pinfunction "1_1") (pintype "passive"))
      (node (ref "C15") (pin "1") (pinfunction "1_1") (pintype "passive"))
      (node (ref "C16") (pin "2") (pinfunction "2_2") (pintype "passive"))
      (node (ref "C2") (pin "2") (pinfunction "2_2") (pintype "passive"))
      (node (ref "C20") (pin "1") (pinfunction "1_1") (pintype "passive"))
      (node (ref "C21") (pin "1") (pinfunction "1_1") (pintype "passive"))
      (node (ref "C22") (pin "1") (pinfunction "1_1") (pintype "passive"))
      (node (ref "C3") (pin "-") (pinfunction "-_-") (pintype "passive"))
      (node (ref "C4") (pin "1") (pinfunction "1_1") (pintype "passive"))
      (node (ref "C5") (pin "2") (pinfunction "2_2") (pintype "passive"))
      (node (ref "C8") (pin "-") (pinfunction "-_-") (pintype "passive"))
      (node (ref "C9") (pin "2") (pinfunction "2_2") (pintype "passive"))
      (node (ref "CAP") (pin "2") (pinfunction "2_2") (pintype "passive"))
      (node (ref "CX1") (pin "2") (pinfunction "2_2") (pintype "passive"))
      (node (ref "CX2") (pin "2") (pinfunction "2_2") (pintype "passive"))
      (node (ref "D1") (pin "A") (pinfunction "A_A") (pintype "passive"))
      (node (ref "EXTPOWER") (pin "1") (pinfunction "1_1") (pintype "power_in"))
      (node (ref "EXTPOWER") (pin "3") (pinfunction "3_3") (pintype "power_in"))
      (node (ref "IC1") (pin "11") (pinfunction "I_11") (pintype "input"))
      (node (ref "IC1") (pin "14") (pinfunction "I_14") (pintype "input"))
      (node (ref "IC1") (pin "8") (pinfunction "VSS_8") (pintype "power_in"))
      (node (ref "IC2") (pin "2") (pinfunction "GND_2") (pintype "bidirectional"))
      (node (ref "IC3") (pin "1") (pinfunction "GND/ADJ_1") (pintype "input"))
      (node (ref "IC4") (pin "4") (pinfunction "V-_4") (pintype "power_in"))
      (node (ref "IC7") (pin "11") (pinfunction "VSSRX_11") (pintype "bidirectional"))
      (node (ref "IC7") (pin "18") (pinfunction "VSSTX_18") (pintype "bidirectional"))
      (node (ref "IC7") (pin "2") (pinfunction "VSS_2") (pintype "bidirectional"))
      (node (ref "IC7") (pin "21") (pinfunction "VSSPLL_21") (pintype "bidirectional"))
      (node (ref "IC7") (pin "22") (pinfunction "VSSOSC_22") (pintype "bidirectional"))
      (node (ref "ICSP") (pin "6") (pinfunction "6_6") (pintype "passive"))
      (node (ref "J1") (pin "S1") (pinfunction "SH1_S1") (pintype "passive"))
      (node (ref "J1") (pin "S2") (pinfunction "SH2_S2") (pintype "passive"))
      (node (ref "J1") (pin "S3") (pinfunction "SH3_S3") (pintype "passive"))
      (node (ref "J1") (pin "S4") (pinfunction "SH4_S4") (pintype "passive"))
      (node (ref "J1") (pin "S5") (pinfunction "SH5_S5") (pintype "passive"))
      (node (ref "J1") (pin "S6") (pinfunction "SH6_S6") (pintype "passive"))
      (node (ref "J3") (pin "6") (pinfunction "6_6") (pintype "passive"))
      (node (ref "J3") (pin "7") (pinfunction "7_7") (pintype "passive"))
      (node (ref "JP1") (pin "3") (pinfunction "3_3") (pintype "passive"))
      (node (ref "JP2") (pin "7") (pinfunction "7_7") (pintype "passive"))
      (node (ref "L") (pin "C") (pinfunction "C_C") (pintype "passive"))
      (node (ref "L2") (pin "2") (pinfunction "2_2") (pintype "passive"))
      (node (ref "ON") (pin "C") (pinfunction "C_C") (pintype "passive"))
      (node (ref "R2") (pin "2") (pinfunction "2_2") (pintype "passive"))
      (node (ref "R3") (pin "1") (pinfunction "1_1") (pintype "passive"))
      (node (ref "RBS") (pin "1") (pinfunction "1_1") (pintype "passive"))
      (node (ref "RESET") (pin "3") (pinfunction "3_3") (pintype "passive"))
      (node (ref "RESET") (pin "4") (pinfunction "4_4") (pintype "passive"))
      (node (ref "RJ1") (pin "G-") (pinfunction "G-_G-") (pintype "bidirectional"))
      (node (ref "RJ1") (pin "GND") (pinfunction "GND_GND") (pintype "bidirectional"))
      (node (ref "RJ1") (pin "SHIELD0") (pinfunction "SHIELD0_SHIELD0") (pintype "bidirectional"))
      (node (ref "RJ1") (pin "SHIELD1") (pinfunction "SHIELD1_SHIELD1") (pintype "bidirectional"))
      (node (ref "RJ1") (pin "Y-") (pinfunction "Y-_Y-") (pintype "bidirectional"))
      (node (ref "RN1") (pin "2") (pinfunction "1_2") (pintype "passive"))
      (node (ref "RN1") (pin "3") (pinfunction "1_3") (pintype "passive"))
      (node (ref "U1") (pin "15") (pinfunction "GND_15") (pintype "power_in"))
      (node (ref "U1") (pin "23") (pinfunction "GND1_23") (pintype "power_in"))
      (node (ref "U1") (pin "35") (pinfunction "GND2_35") (pintype "power_in"))
      (node (ref "U1") (pin "EXP") (pinfunction "PAD_EXP") (pintype "power_in"))
      (node (ref "U2") (pin "15") (pinfunction "GND_15") (pintype "power_in"))
      (node (ref "U2") (pin "23") (pinfunction "GND1_23") (pintype "power_in"))
      (node (ref "U2") (pin "35") (pinfunction "GND2_35") (pintype "power_in"))
      (node (ref "U2") (pin "P$1") (pinfunction "PAD_P$1") (pintype "power_in"))
      (node (ref "U3") (pin "2") (pinfunction "GND_2") (pintype "power_in"))
      (node (ref "X1") (pin "6") (pinfunction "VSS_6") (pintype "power_in"))
      (node (ref "X1") (pin "MT1") (pinfunction "GND_MT1") (pintype "power_in"))
      (node (ref "X1") (pin "MT2") (pinfunction "GND1_MT2") (pintype "power_in"))
      (node (ref "Y1") (pin "2") (pinfunction "GND_2") (pintype "passive"))
      (node (ref "Y1") (pin "4") (pinfunction "GND_4") (pintype "passive"))
      (node (ref "Z1") (pin "2") (pinfunction "2_2") (pintype "passive"))
      (node (ref "Z2") (pin "2") (pinfunction "2_2") (pintype "passive"))
    )
    (net (code "66") (name "Net-(ACT-PadC)") (class "Default")
      (node (ref "ACT") (pin "C") (pinfunction "C_C") (pintype "passive"))
      (node (ref "R4") (pin "2") (pinfunction "2_2") (pintype "passive"))
    )
    (net (code "67") (name "Net-(IC1A-O)") (class "Default")
      (node (ref "IC1") (pin "2") (pinfunction "O_2") (pintype "output"))
      (node (ref "X1") (pin "5") (pinfunction "SCLK_5") (pintype "input"))
    )
    (net (code "68") (name "Net-(IC1B-O)") (class "Default")
      (node (ref "IC1") (pin "4") (pinfunction "O_4") (pintype "output"))
      (node (ref "X1") (pin "3") (pinfunction "DATA_IN_3") (pintype "input"))
    )
    (net (code "69") (name "Net-(IC1C-O)") (class "Default")
      (node (ref "IC1") (pin "6") (pinfunction "O_6") (pintype "output"))
      (node (ref "R4") (pin "1") (pinfunction "1_1") (pintype "passive"))
      (node (ref "X1") (pin "2") (pinfunction "CS_2") (pintype "input"))
    )
    (net (code "70") (name "Net-(IC1D-O)") (class "Default")
      (node (ref "ACT") (pin "A") (pinfunction "A_A") (pintype "passive"))
      (node (ref "IC1") (pin "10") (pinfunction "O_10") (pintype "output"))
    )
    (net (code "71") (name "Net-(IC7-LEDA)") (class "Default")
      (node (ref "IC7") (pin "27") (pinfunction "LEDA_27") (pintype "bidirectional"))
      (node (ref "R5") (pin "1") (pinfunction "1_1") (pintype "passive"))
    )
    (net (code "72") (name "Net-(IC7-LEDB)") (class "Default")
      (node (ref "IC7") (pin "26") (pinfunction "LEDB_26") (pintype "bidirectional"))
      (node (ref "R6") (pin "1") (pinfunction "1_1") (pintype "passive"))
    )
    (net (code "73") (name "Net-(IC7-OSC1)") (class "Default")
      (node (ref "CX2") (pin "1") (pinfunction "1_1") (pintype "passive"))
      (node (ref "IC7") (pin "23") (pinfunction "OSC1_23") (pintype "bidirectional"))
      (node (ref "X2A") (pin "P$1") (pinfunction "1_P$1") (pintype "passive"))
      (node (ref "X2A1") (pin "1") (pinfunction "1_1") (pintype "passive"))
    )
    (net (code "74") (name "Net-(IC7-OSC2)") (class "Default")
      (node (ref "CX1") (pin "1") (pinfunction "1_1") (pintype "passive"))
      (node (ref "IC7") (pin "24") (pinfunction "OSC2_24") (pintype "bidirectional"))
      (node (ref "X2A") (pin "P$2") (pinfunction "2_P$2") (pintype "passive"))
      (node (ref "X2A1") (pin "2") (pinfunction "2_2") (pintype "passive"))
    )
    (net (code "75") (name "Net-(IC7-RBIAS)") (class "Default")
      (node (ref "IC7") (pin "14") (pinfunction "RBIAS_14") (pintype "bidirectional"))
      (node (ref "RBS") (pin "2") (pinfunction "2_2") (pintype "passive"))
    )
    (net (code "76") (name "Net-(IC7-VCAP)") (class "Default")
      (node (ref "CAP") (pin "1") (pinfunction "1_1") (pintype "passive"))
      (node (ref "IC7") (pin "1") (pinfunction "VCAP_1") (pintype "bidirectional"))
    )
    (net (code "77") (name "Net-(LCD-RW)") (class "Default")
      (node (ref "LCD") (pin "1") (pinfunction "VSS_1") (pintype "power_in"))
      (node (ref "LCD") (pin "5") (pinfunction "RW_5") (pintype "input"))
    )
    (net (code "78") (name "Net-(RN2A-2)") (class "Default")
      (node (ref "ON") (pin "A") (pinfunction "A_A") (pintype "passive"))
      (node (ref "RN2") (pin "8") (pinfunction "2_8") (pintype "passive"))
    )
    (net (code "79") (name "Net-(RN2B-2)") (class "Default")
      (node (ref "L") (pin "A") (pinfunction "A_A") (pintype "passive"))
      (node (ref "RN2") (pin "7") (pinfunction "2_7") (pintype "passive"))
    )
    (net (code "80") (name "Net-(RN2C-2)") (class "Default")
      (node (ref "RN2") (pin "6") (pinfunction "2_6") (pintype "passive"))
      (node (ref "TX") (pin "A") (pinfunction "A_A") (pintype "passive"))
    )
    (net (code "81") (name "Net-(RN2D-2)") (class "Default")
      (node (ref "RN2") (pin "5") (pinfunction "2_5") (pintype "passive"))
      (node (ref "RX") (pin "A") (pinfunction "A_A") (pintype "passive"))
    )
    (net (code "82") (name "Net-(RN4C-2)") (class "Default")
      (node (ref "C21") (pin "2") (pinfunction "2_2") (pintype "passive"))
      (node (ref "RN4") (pin "5") (pinfunction "2_5") (pintype "passive"))
      (node (ref "RN4") (pin "6") (pinfunction "2_6") (pintype "passive"))
    )
    (net (code "83") (name "UGND") (class "Default")
      (node (ref "C7") (pin "2") (pinfunction "2_2") (pintype "passive"))
      (node (ref "J1") (pin "P5") (pinfunction "GND_P5") (pintype "passive"))
      (node (ref "L2") (pin "1") (pinfunction "1_1") (pintype "passive"))
      (node (ref "R3") (pin "2") (pinfunction "2_2") (pintype "passive"))
      (node (ref "U1") (pin "5") (pinfunction "UGND_5") (pintype "power_in"))
      (node (ref "U2") (pin "5") (pinfunction "UGND_5") (pintype "power_in"))
    )
    (net (code "84") (name "VCC") (class "Default")
      (node (ref "C9") (pin "1") (pinfunction "1_1") (pintype "passive"))
      (node (ref "IC2") (pin "1") (pinfunction "VIN_1") (pintype "bidirectional"))
      (node (ref "IC2") (pin "3") (pinfunction "EN_3") (pintype "bidirectional"))
      (node (ref "IC7") (pin "15") (pinfunction "VDDTX_15") (pintype "bidirectional"))
      (node (ref "IC7") (pin "19") (pinfunction "VDDRX_19") (pintype "bidirectional"))
      (node (ref "IC7") (pin "20") (pinfunction "VDDPLL_20") (pintype "bidirectional"))
      (node (ref "IC7") (pin "25") (pinfunction "VDDOSC_25") (pintype "bidirectional"))
      (node (ref "IC7") (pin "28") (pinfunction "VDD_28") (pintype "bidirectional"))
      (node (ref "JP1") (pin "1") (pinfunction "1_1") (pintype "passive"))
      (node (ref "L5") (pin "2") (pinfunction "2_2") (pintype "passive"))
    )
    (net (code "85") (name "VUSB") (class "Default")
      (node (ref "C3") (pin "+") (pinfunction "+_+") (pintype "passive"))
      (node (ref "C4") (pin "2") (pinfunction "2_2") (pintype "passive"))
      (node (ref "F1") (pin "1") (pinfunction "1_1") (pintype "passive"))
      (node (ref "T1") (pin "1") (pinfunction "D_1") (pintype "passive"))
      (node (ref "U1") (pin "7") (pinfunction "VBUS_7") (pintype "input"))
      (node (ref "U2") (pin "7") (pinfunction "VBUS_7") (pintype "input"))
    )
    (net (code "86") (name "unconnected-(IC1E-O-Pad12)") (class "Default")
      (node (ref "IC1") (pin "12") (pinfunction "O_12") (pintype "output"))
    )
    (net (code "87") (name "unconnected-(IC1F-O-Pad15)") (class "Default")
      (node (ref "IC1") (pin "15") (pinfunction "O_15") (pintype "output"))
    )
    (net (code "88") (name "unconnected-(IC2-BYP-Pad4)") (class "Default")
      (node (ref "IC2") (pin "4") (pinfunction "BYP_4") (pintype "bidirectional"))
    )
    (net (code "89") (name "unconnected-(IC7-CLKOUT-Pad3)") (class "Default")
      (node (ref "IC7") (pin "3") (pinfunction "CLKOUT_3") (pintype "bidirectional"))
    )
    (net (code "90") (name "unconnected-(IC7-NC-Pad5)") (class "Default")
      (node (ref "IC7") (pin "5") (pinfunction "NC_5") (pintype "bidirectional"))
    )
    (net (code "91") (name "unconnected-(IC7-{slash}INT-Pad4)") (class "Default")
      (node (ref "IC7") (pin "4") (pinfunction "/INT_4") (pintype "bidirectional"))
    )
    (net (code "92") (name "unconnected-(J3-Pad1)") (class "Default")
      (node (ref "J3") (pin "1") (pinfunction "1_1") (pintype "passive"))
    )
    (net (code "93") (name "unconnected-(LCD-A-Pad15)") (class "Default")
      (node (ref "LCD") (pin "15") (pinfunction "A_15") (pintype "input"))
    )
    (net (code "94") (name "unconnected-(LCD-DB0-Pad7)") (class "Default")
      (node (ref "LCD") (pin "7") (pinfunction "DB0_7") (pintype "bidirectional"))
    )
    (net (code "95") (name "unconnected-(LCD-DB1-Pad8)") (class "Default")
      (node (ref "LCD") (pin "8") (pinfunction "DB1_8") (pintype "bidirectional"))
    )
    (net (code "96") (name "unconnected-(LCD-DB2-Pad9)") (class "Default")
      (node (ref "LCD") (pin "9") (pinfunction "DB2_9") (pintype "bidirectional"))
    )
    (net (code "97") (name "unconnected-(LCD-DB3-Pad10)") (class "Default")
      (node (ref "LCD") (pin "10") (pinfunction "DB3_10") (pintype "bidirectional"))
    )
    (net (code "98") (name "unconnected-(LCD-K-Pad16)") (class "Default")
      (node (ref "LCD") (pin "16") (pinfunction "K_16") (pintype "input"))
    )
    (net (code "99") (name "unconnected-(ORIGIN-TESTP-PadX)") (class "Default")
      (node (ref "ORIGIN") (pin "X") (pinfunction "TESTP_X") (pintype "passive"))
    )
    (net (code "100") (name "unconnected-(RJ1-PadNC)") (class "Default")
      (node (ref "RJ1") (pin "NC") (pinfunction "NC_NC") (pintype "bidirectional"))
    )
    (net (code "101") (name "unconnected-(RJ1-PadP5)") (class "Default")
      (node (ref "RJ1") (pin "P5") (pinfunction "P5_P5") (pintype "bidirectional"))
    )
    (net (code "102") (name "unconnected-(RN3B-1-Pad2)") (class "Default")
      (node (ref "RN3") (pin "2") (pinfunction "1_2") (pintype "passive"))
    )
    (net (code "103") (name "unconnected-(RN3B-2-Pad7)") (class "Default")
      (node (ref "RN3") (pin "7") (pinfunction "2_7") (pintype "passive"))
    )
    (net (code "104") (name "unconnected-(RN3C-1-Pad3)") (class "Default")
      (node (ref "RN3") (pin "3") (pinfunction "1_3") (pintype "passive"))
    )
    (net (code "105") (name "unconnected-(RN3C-2-Pad6)") (class "Default")
      (node (ref "RN3") (pin "6") (pinfunction "2_6") (pintype "passive"))
    )
    (net (code "106") (name "unconnected-(U3-NC{slash}FB-Pad4)") (class "Default")
      (node (ref "U3") (pin "4") (pinfunction "NC/FB_4") (pintype "passive"))
    )
    (net (code "107") (name "unconnected-(X1-CARD_DETECT1-PadCD2)") (class "Default")
      (node (ref "X1") (pin "CD2") (pinfunction "CARD_DETECT1_CD2") (pintype "passive"))
    )
    (net (code "108") (name "unconnected-(X1-DAT1-Pad8)") (class "Default")
      (node (ref "X1") (pin "8") (pinfunction "DAT1_8") (pintype "bidirectional"))
    )
    (net (code "109") (name "unconnected-(X1-DAT2-Pad1)") (class "Default")
      (node (ref "X1") (pin "1") (pinfunction "DAT2_1") (pintype "bidirectional"))
    )
  )
)
